# ELOAD.net
KiCad netlist of a schematic drawn in Altium Designer
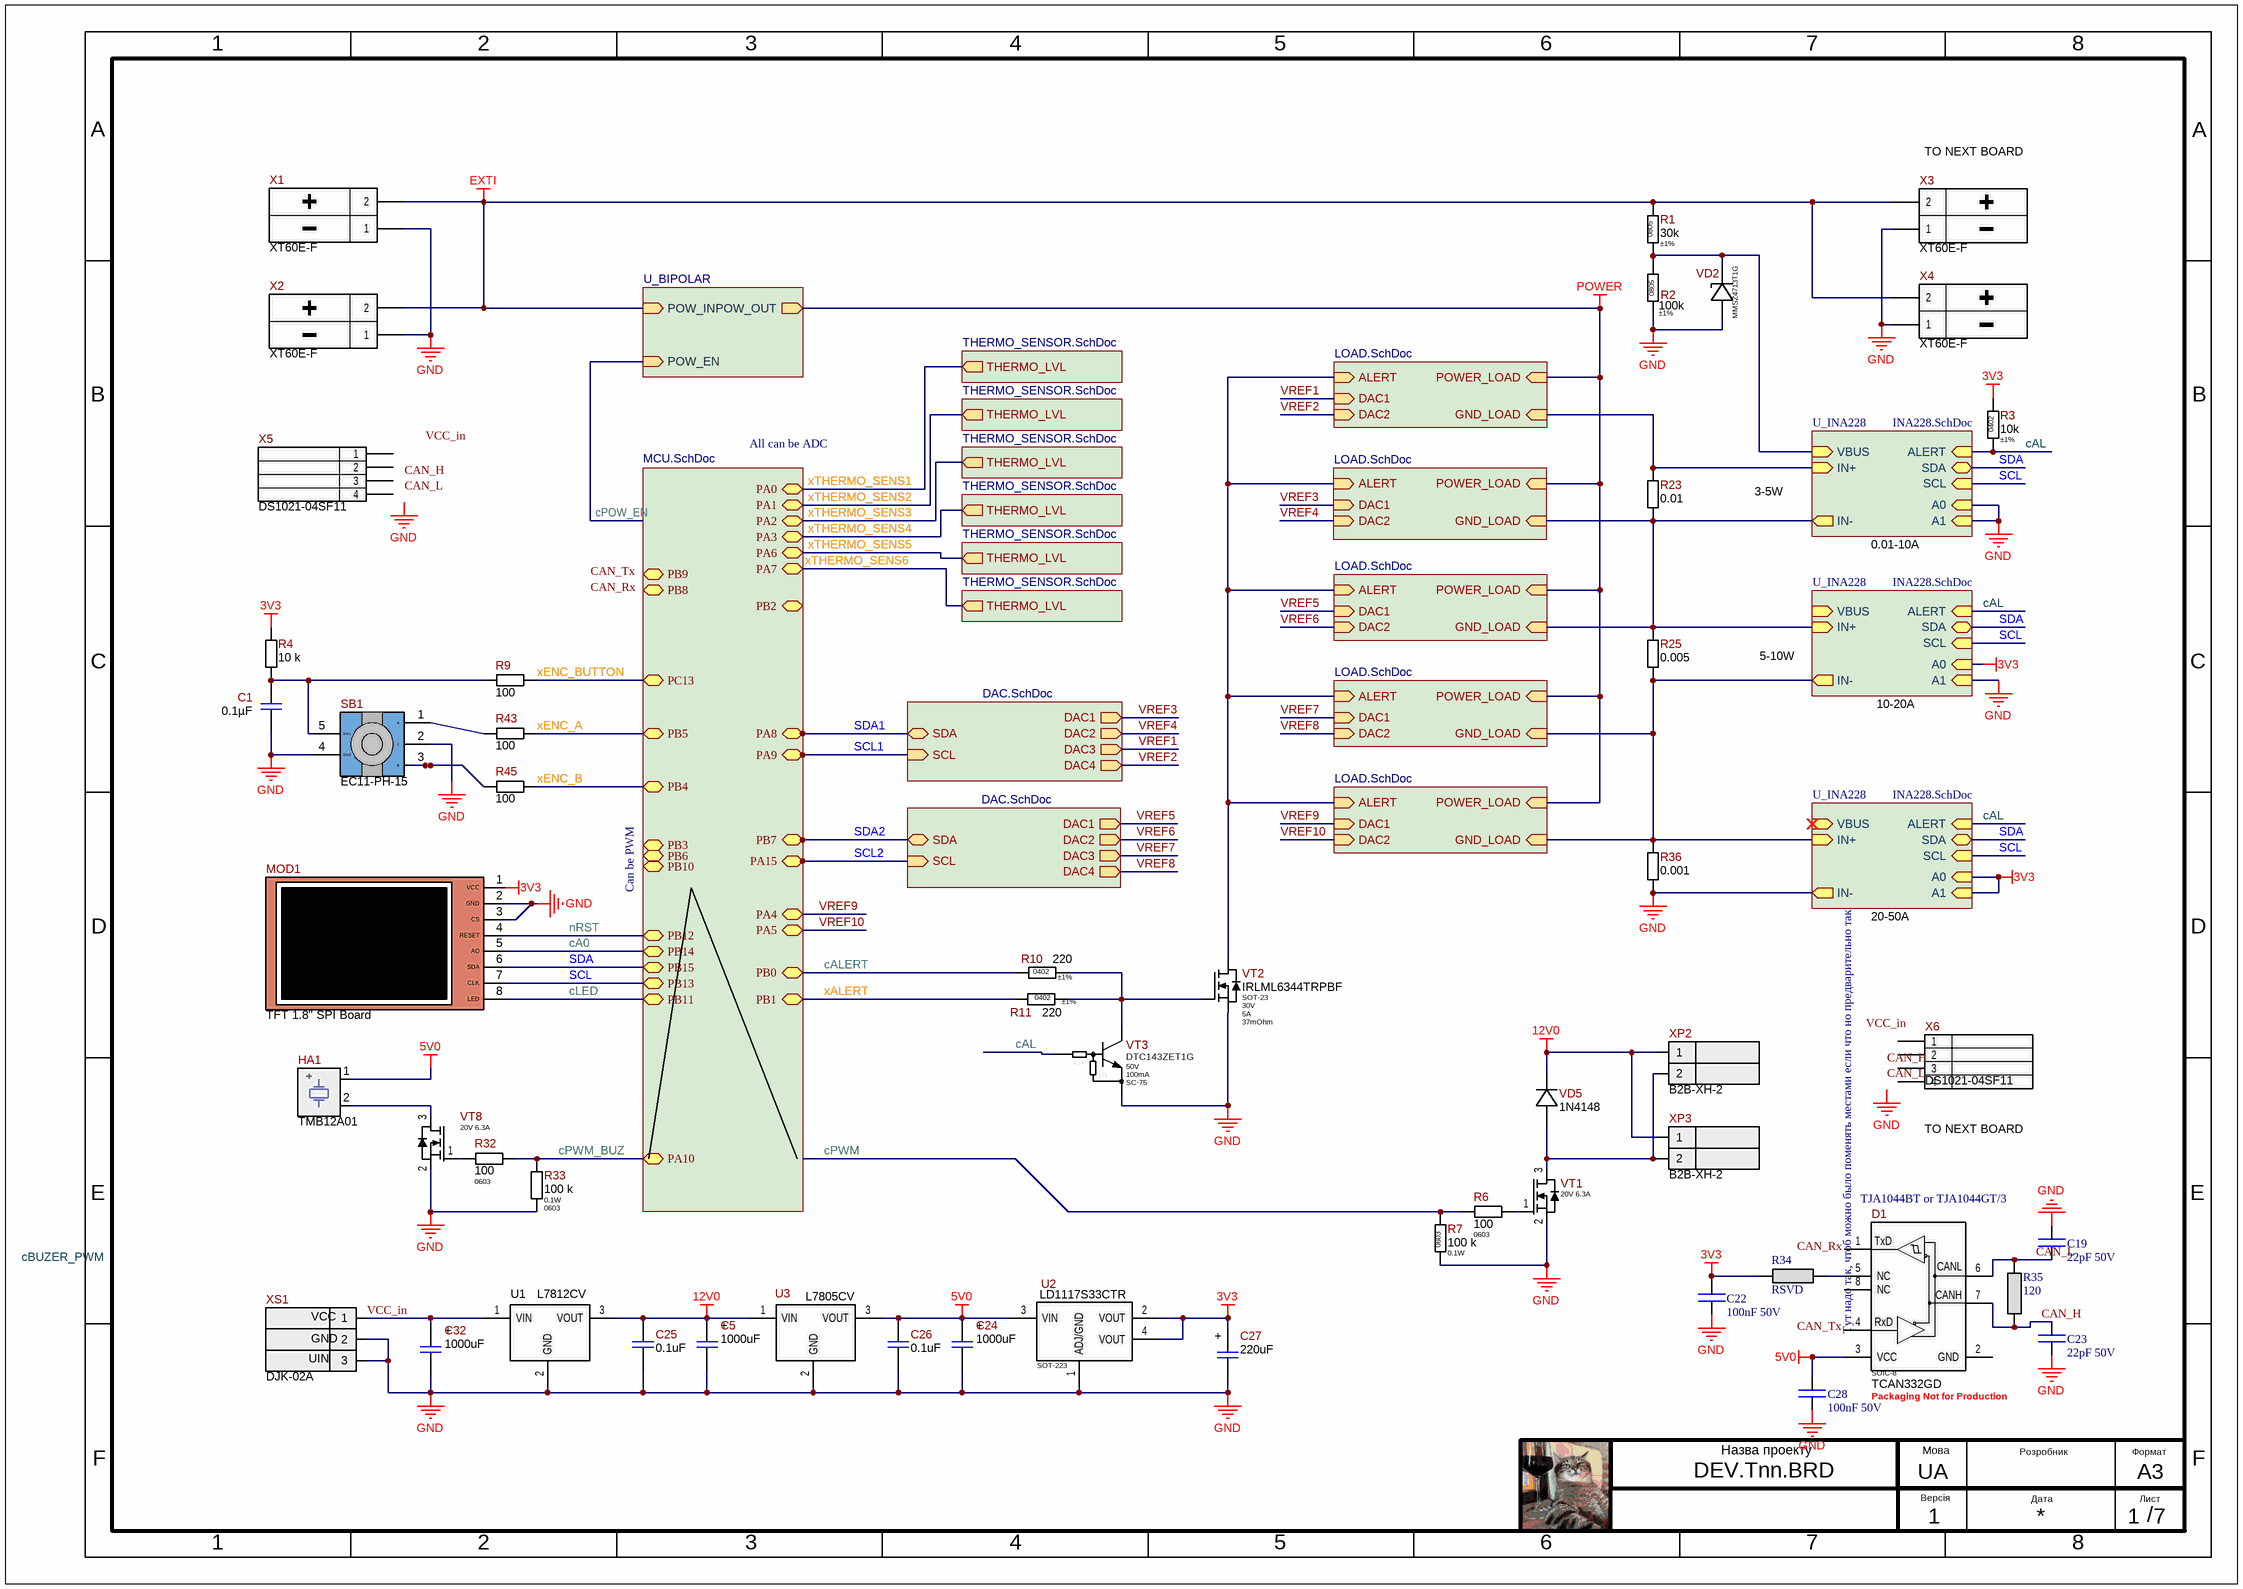
[diagram p0: ELOAD.SchDoc]

(export (version "E")
  (design (tool "Eeschema 10.0.6"))
  (components
    (comp (ref "C1")
      (value "0.1µF")
      (footprint "C0603(1608)")
      (description "CAP CER 0.1UF 50V X7R 0603")
      (fields (field (name "PART NUMBER") "0.1µF  50V C0603") (field (name "TOLERANCE") "±10%"))
      (libsource (lib "Database") (part "Capacitor_Ceramic"))
    )
    (comp (ref "C5")
      (value "1000uF")
      (footprint "CAP 10x16")
      (description "1000uF 20% 16V EHR 10x16mm")
      (fields (field (name "PART NUMBER") "1000uF  16V 10x16(EHR)") (field (name "TOLERANCE") "±20%"))
      (libsource (lib "Database") (part "Capacitor_Electrolytic"))
    )
    (comp (ref "C19")
      (value "22pF 50V")
      (footprint "0805CAP")
      (description "0805 CAP 100nF 50V")
      (libsource (lib "newLib") (part "CAP0805"))
    )
    (comp (ref "C22")
      (value "100nF 50V")
      (footprint "0805CAP")
      (description "0805 CAP 100nF 50V")
      (libsource (lib "newLib") (part "CAP0805"))
    )
    (comp (ref "C23")
      (value "22pF 50V")
      (footprint "0805CAP")
      (description "0805 CAP 100nF 50V")
      (libsource (lib "newLib") (part "CAP0805"))
    )
    (comp (ref "C24")
      (value "1000uF")
      (footprint "CAP 10x16")
      (description "1000uF 20% 16V EHR 10x16mm")
      (fields (field (name "PART NUMBER") "1000uF  16V 10x16(EHR)") (field (name "TOLERANCE") "±20%"))
      (libsource (lib "Database") (part "Capacitor_Electrolytic"))
    )
    (comp (ref "C25")
      (value "0.1uF")
      (footprint "C0603(1608)")
      (description "CAP CER 0.1UF 50V X7R 0603")
      (fields (field (name "PART NUMBER") "0.1uF  50V C0603") (field (name "TOLERANCE") "±10%"))
      (libsource (lib "Database") (part "Capacitor_Ceramic"))
    )
    (comp (ref "C26")
      (value "0.1uF")
      (footprint "C0603(1608)")
      (description "CAP CER 0.1UF 50V X7R 0603")
      (fields (field (name "PART NUMBER") "0.1uF  50V C0603") (field (name "TOLERANCE") "±10%"))
      (libsource (lib "Database") (part "Capacitor_Ceramic"))
    )
    (comp (ref "C27")
      (value "220uF")
      (footprint "CASE_D(7343)")
      (description "CAP TANT 220UF 20% 10V 2917")
      (fields (field (name "PART NUMBER") "220uF  10V CASE-D") (field (name "TOLERANCE") "±20%"))
      (libsource (lib "Database") (part "Capacitor_Electrolytic"))
    )
    (comp (ref "C28")
      (value "100nF 50V")
      (footprint "0805CAP")
      (description "0805 CAP 100nF 50V")
      (libsource (lib "newLib") (part "CAP0805"))
    )
    (comp (ref "C32")
      (value "1000uF")
      (footprint "CAP 10x16")
      (description "1000uF 20% 16V EHR 10x16mm")
      (fields (field (name "PART NUMBER") "1000uF  16V 10x16(EHR)") (field (name "TOLERANCE") "±20%"))
      (libsource (lib "Database") (part "Capacitor_Electrolytic"))
    )
    (comp (ref "D1")
      (value "TCAN332GD")
      (footprint "SOIC-8_W3.9MM")
      (description "3.3V Half Duplex CAN Transceivers with CAN FD, 5 Mbps, SOIC-8")
      (fields
        (field (name "PACKAGE") "SOIC-8")
        (field (name "PART NUMBER") "TCAN332GD")
        (field (name "LIFECYCLE") "Packaging Not for Production")
        (field (name "MANUFACTURER") "Texas Instruments")
      )
      (libsource (lib "AjaxLibrary") (part "TCAN332xx"))
    )
    (comp (ref "HA1")
      (value "TMB12A01")
      (footprint "KPX-1205A")
      (description "AUDIO MAGNETIC 1.2-2.5 V")
      (libsource (lib "Database") (part "BUZ"))
    )
    (comp (ref "MOD1")
      (value "TFT 1.8\" SPI Board")
      (footprint "1.8_TFT_BOARD")
      (description "Display Board TFT 1.8\" SPI Driver ST7735S with SD")
      (libsource (lib "Database") (part "DIS_TFT_1.8"))
    )
    (comp (ref "R1")
      (value "30k")
      (footprint "R_ANY_CHIP_0805_MED")
      (description "30 kOhms ±1%, 1/8W 0805 Thick Film Resistor")
      (fields
        (field (name "TOLERANCE") "±1%")
        (field (name "PACKAGE") "0805")
        (field (name "PART NUMBER") "RC0805FR-0730KL")
        (field (name "MANUFACTURER") "Yageo")
      )
      (libsource (lib "AjaxLibrary") (part "Resistor"))
    )
    (comp (ref "R2")
      (value "100k")
      (footprint "R_ANY_CHIP_0805_MED")
      (description "100 kOhms ±1%, 1/8W 0805 Thick Film Resistor")
      (fields
        (field (name "TOLERANCE") "±1%")
        (field (name "PACKAGE") "0805")
        (field (name "PART NUMBER") "RC0805FR-07100KL")
        (field (name "MANUFACTURER") "Yageo")
      )
      (libsource (lib "AjaxLibrary") (part "Resistor"))
    )
    (comp (ref "R3")
      (value "10k")
      (footprint "R_ANY_CHIP_0402_MED")
      (description "220 Ohms ±1% 1/16W 0402 Thick Film Resistor")
      (fields
        (field (name "TOLERANCE") "±1%")
        (field (name "PACKAGE") "0402")
        (field (name "PART NUMBER") "RC0402FR-07220RL")
        (field (name "MANUFACTURER") "Yageo")
      )
      (libsource (lib "AjaxLibrary") (part "Resistor"))
    )
    (comp (ref "R4")
      (value "10 k")
      (footprint "R0603")
      (description "RES SMD 10 k OHM  ±1% 1/10W 0603")
      (fields (field (name "PART NUMBER") "10 k  R0603"))
      (libsource (lib "Database") (part "R0603"))
    )
    (comp (ref "R6")
      (value "100")
      (footprint "R0603")
      (description "RES SMD 100 OHM  ±1% 1/10W 0603")
      (fields
        (field (name "PACKAGE/CASE") "0603")
        (field (name "PART NUMBER") "100  R0603")
        (field (name "TOLERANCE") "±1%")
      )
      (libsource (lib "Database") (part "R0603"))
    )
    (comp (ref "R7")
      (value "100 k")
      (footprint "R0603")
      (description "RES SMD 100 k OHM  ±1% 1/10W 0603")
      (fields
        (field (name "POWER RATING") "0.1W")
        (field (name "PACKAGE/CASE") "0603")
        (field (name "PART NUMBER") "100 k  R0603")
        (field (name "TOLERANCE") "±1%")
      )
      (libsource (lib "Database") (part "R0603"))
    )
    (comp (ref "R9")
      (value "100")
      (footprint "R0603")
      (description "RES SMD 100 OHM  ±1% 1/10W 0603")
      (fields (field (name "PART NUMBER") "100  R0603") (field (name "TOLERANCE") "±1%"))
      (libsource (lib "Database") (part "R0603"))
    )
    (comp (ref "R10")
      (value "220")
      (footprint "R_ANY_CHIP_0402_MED")
      (description "220 Ohms ±1% 1/16W 0402 Thick Film Resistor")
      (fields
        (field (name "TOLERANCE") "±1%")
        (field (name "PACKAGE") "0402")
        (field (name "PART NUMBER") "RC0402FR-07220RL")
        (field (name "MANUFACTURER") "Yageo")
      )
      (libsource (lib "AjaxLibrary") (part "Resistor"))
    )
    (comp (ref "R11")
      (value "220")
      (footprint "R_ANY_CHIP_0402_MED")
      (description "220 Ohms ±1% 1/16W 0402 Thick Film Resistor")
      (fields
        (field (name "TOLERANCE") "±1%")
        (field (name "PACKAGE") "0402")
        (field (name "PART NUMBER") "RC0402FR-07220RL")
        (field (name "MANUFACTURER") "Yageo")
      )
      (libsource (lib "AjaxLibrary") (part "Resistor"))
    )
    (comp (ref "R23")
      (value "0.01")
      (footprint "SHUNT10")
      (description "SHUNT")
      (fields (field (name "PART NUMBER") "0.001  Resistor") (field (name "TOLERANCE") "±5%"))
      (libsource (lib "Database") (part "RESISTOR"))
    )
    (comp (ref "R25")
      (value "0.005")
      (footprint "SHUNT10")
      (description "SHUNT")
      (fields (field (name "PART NUMBER") "0.001  Resistor") (field (name "TOLERANCE") "±5%"))
      (libsource (lib "Database") (part "RESISTOR"))
    )
    (comp (ref "R32")
      (value "100")
      (footprint "R0603")
      (description "RES SMD 100 OHM  ±1% 1/10W 0603")
      (fields
        (field (name "PACKAGE/CASE") "0603")
        (field (name "PART NUMBER") "100  R0603")
        (field (name "TOLERANCE") "±1%")
      )
      (libsource (lib "Database") (part "R0603"))
    )
    (comp (ref "R33")
      (value "100 k")
      (footprint "R0603")
      (description "RES SMD 100 k OHM  ±1% 1/10W 0603")
      (fields
        (field (name "POWER RATING") "0.1W")
        (field (name "PACKAGE/CASE") "0603")
        (field (name "PART NUMBER") "100 k  R0603")
        (field (name "TOLERANCE") "±1%")
      )
      (libsource (lib "Database") (part "R0603"))
    )
    (comp (ref "R34")
      (value "RSVD")
      (footprint "RES0402")
      (description "0402 RES 10k")
      (libsource (lib "newLib") (part "RES0402"))
    )
    (comp (ref "R35")
      (value "120")
      (footprint "Res0805")
      (description "0805 RES 120")
      (libsource (lib "newLib") (part "RES0805"))
    )
    (comp (ref "R36")
      (value "0.001")
      (footprint "SHUNT10")
      (description "SHUNT")
      (fields (field (name "PART NUMBER") "0.001  Resistor") (field (name "TOLERANCE") "±5%"))
      (libsource (lib "Database") (part "RESISTOR"))
    )
    (comp (ref "R43")
      (value "100")
      (footprint "R0603")
      (description "RES SMD 100 OHM  ±1% 1/10W 0603")
      (fields (field (name "PART NUMBER") "100  R0603") (field (name "TOLERANCE") "±1%"))
      (libsource (lib "Database") (part "R0603"))
    )
    (comp (ref "R45")
      (value "100")
      (footprint "R0603")
      (description "RES SMD 100 OHM  ±1% 1/10W 0603")
      (fields (field (name "PART NUMBER") "100  R0603") (field (name "TOLERANCE") "±1%"))
      (libsource (lib "Database") (part "R0603"))
    )
    (comp (ref "SB1")
      (value "EC11-PH-15")
      (footprint "EC11-PH-15")
      (description "Alps Alpine")
      (libsource (lib "Database") (part "Encoder"))
    )
    (comp (ref "U1")
      (value "L7812CV")
      (footprint "TO220-AB-H")
      (description "IC REG LINEAR 12V 500MA DPAK")
      (fields (field (name "MANUFACTURER") "STMicroelectronics"))
      (libsource (lib "Database") (part "L78"))
    )
    (comp (ref "U2")
      (value "LD1117STR")
      (footprint "SOT223")
      (description "IC REG LINEAR 3.3V 800MA SOT223")
      (fields
        (field (name "MANUFACTURER") "STMicroelectronics")
        (field (name "PACKAGE") "SOT-223")
        (field (name "PART NUMBER") "LD1117S33CTR")
      )
      (libsource (lib "Database") (part "LD1117S"))
    )
    (comp (ref "U3")
      (value "L7805CV")
      (footprint "DPAK")
      (description "IC REG LINEAR 5V 1.5A DPAK")
      (fields (field (name "MANUFACTURER") "STMicroelectronics"))
      (libsource (lib "Database") (part "L78"))
    )
    (comp (ref "VD2")
      (value "MMSZ4713T1G")
      (footprint "SOD-123_MED")
      (description "Zener Diode 30V, 500mW, ±5%, SOD-123")
      (fields
        (field (name "PART NUMBER") "MMSZ4713T1G")
        (field (name "VOLTAGE") "30V")
        (field (name "MANUFACTURER") "Onsemi")
      )
      (libsource (lib "AjaxLibrary") (part "Diode-Zener"))
    )
    (comp (ref "VD5")
      (value "1N4148")
      (footprint "D0805")
      (description "DIODE GEN PURP 75V 250MA SOD323")
      (fields (field (name "MANUFACTURER") "Diodes Incorporated"))
      (libsource (lib "Database") (part "DIODE"))
    )
    (comp (ref "VT1")
      (value "IRLML6244")
      (footprint "SOT-23")
      (description "MOSFET N-CH 20V 6.3A SOT-23")
      (fields (field (name "POWER RATING") "20V 6.3A") (field (name "MANUFACTURER") "InfineonTechnologies"))
      (libsource (lib "Database") (part "N_CHANNEL"))
    )
    (comp (ref "VT2")
      (value "IRLML6344")
      (footprint "SOT-23_MED")
      (description "30V, 5A max N-Channel HEXFET MOSFET, 29mOhm @ Vgs = 4.5V")
      (fields
        (field (name "PART NUMBER") "IRLML6344TRPBF")
        (field (name "PACKAGE") "SOT-23")
        (field (name "MANUFACTURER") "Infineon Technologies")
        (field (name "VDS") "30V")
        (field (name "ID") "5A")
        (field (name "RDS") "37mOhm")
      )
      (libsource (lib "AjaxLibrary") (part "MOSFET-N-Channel"))
    )
    (comp (ref "VT3")
      (value "DTC143ZET1G")
      (footprint "SOT-416")
      (description "50V, 100mA Low Vce(sat) NPN Digital Transistor, Pre-Biased 4.7k/47k (with built-in resistors)")
      (fields
        (field (name "PART NUMBER") "DTC143ZET1G")
        (field (name "VCE") "50V")
        (field (name "IC") "100mA")
        (field (name "PACKAGE") "SC-75")
        (field (name "MANUFACTURER") "Onsemi")
      )
      (libsource (lib "AjaxLibrary") (part "DTC143ZET1G"))
    )
    (comp (ref "VT8")
      (value "IRLML6244")
      (footprint "SOT-23")
      (description "MOSFET N-CH 20V 6.3A SOT-23")
      (fields (field (name "POWER RATING") "20V 6.3A") (field (name "MANUFACTURER") "InfineonTechnologies"))
      (libsource (lib "Database") (part "N_CHANNEL"))
    )
    (comp (ref "X1")
      (value "XT60E-F")
      (footprint "XT60E-F")
      (description "2 Pin DC Power Socket, XT60, Female, Straight, Yellow, 30A, 500V, Gold Flash")
      (fields (field (name "PART NUMBER") "XT60E-F") (field (name "MANUFACTURER") "Amass"))
      (libsource (lib "AjaxLibrary") (part "XT60-Series"))
    )
    (comp (ref "X2")
      (value "XT60E-F")
      (footprint "XT60E-F")
      (description "2 Pin DC Power Socket, XT60, Female, Straight, Yellow, 30A, 500V, Gold Flash")
      (fields (field (name "PART NUMBER") "XT60E-F") (field (name "MANUFACTURER") "Amass"))
      (libsource (lib "AjaxLibrary") (part "XT60-Series"))
    )
    (comp (ref "X3")
      (value "XT60E-F")
      (footprint "XT60E-F")
      (description "2 Pin DC Power Socket, XT60, Female, Straight, Yellow, 30A, 500V, Gold Flash")
      (fields (field (name "PART NUMBER") "XT60E-F") (field (name "MANUFACTURER") "Amass"))
      (libsource (lib "") (part "XT60-Series_1"))
    )
    (comp (ref "X4")
      (value "XT60E-F")
      (footprint "XT60E-F")
      (description "2 Pin DC Power Socket, XT60, Female, Straight, Yellow, 30A, 500V, Gold Flash")
      (fields (field (name "PART NUMBER") "XT60E-F") (field (name "MANUFACTURER") "Amass"))
      (libsource (lib "") (part "XT60-Series_1"))
    )
    (comp (ref "X5")
      (value "PLS-4 (Part of PLS-40)")
      (footprint "DS1021-04S")
      (description "4 Pin 2.54mm Male Header, Vertical, 3mm and 6.1mm, PLS-4")
      (fields (field (name "PART NUMBER") "DS1021-04SF11") (field (name "MANUFACTURER") "Connfly"))
      (libsource (lib "") (part "General-4-Pin_1"))
    )
    (comp (ref "X6")
      (value "PLS-4 (Part of PLS-40)")
      (footprint "DS1021-04S")
      (description "4 Pin 2.54mm Male Header, Vertical, 3mm and 6.1mm, PLS-4")
      (fields (field (name "PART NUMBER") "DS1021-04SF11") (field (name "MANUFACTURER") "Connfly"))
      (libsource (lib "AjaxLibrary") (part "General-4-Pin"))
    )
    (comp (ref "XP2")
      (value "B2B-XH-2")
      (footprint "B2B-XH-2")
      (description "CONN HEADER VERT 2POS 2.5MM")
      (fields (field (name "MANUFACTURER") "JSTSalesAmericaInc."))
      (libsource (lib "Database") (part "CON_2"))
    )
    (comp (ref "XP3")
      (value "B2B-XH-2")
      (footprint "B2B-XH-2")
      (description "CONN HEADER VERT 2POS 2.5MM")
      (fields (field (name "MANUFACTURER") "JSTSalesAmericaInc."))
      (libsource (lib "Database") (part "CON_2"))
    )
    (comp (ref "XS1")
      (value "DJK-02A")
      (footprint "DC-140-003")
      (description "DC POWER JACK CONNECTOR 6.3MM")
      (fields (field (name "MANUFACTURER") "KLS"))
      (libsource (lib "Database") (part "DJK-02A"))
    )
  )
  (nets
    (net (code "1") (name "/ALERT") (class "Default")
      (node (ref "VT2") (pin "3") (pinfunction "D_3") (pintype "passive"))
    )
    (net (code "2") (name "/CAN_H") (class "Default")
      (node (ref "C23") (pin "2") (pinfunction "2_2") (pintype "passive"))
      (node (ref "D1") (pin "7") (pinfunction "CANH_7") (pintype "passive"))
      (node (ref "R35") (pin "1") (pinfunction "1_1") (pintype "passive"))
    )
    (net (code "3") (name "/CAN_L") (class "Default")
      (node (ref "C19") (pin "1") (pinfunction "1_1") (pintype "passive"))
      (node (ref "D1") (pin "6") (pinfunction "CANL_6") (pintype "passive"))
      (node (ref "R35") (pin "2") (pinfunction "2_2") (pintype "passive"))
    )
    (net (code "6") (name "/GND_LOAD") (class "Default")
      (node (ref "R23") (pin "2") (pinfunction "2_2") (pintype "passive"))
    )
    (net (code "7") (name "/IN-") (class "Default")
      (node (ref "R23") (pin "1") (pinfunction "1_1") (pintype "passive"))
      (node (ref "R25") (pin "2") (pinfunction "2_2") (pintype "passive"))
    )
    (net (code "8") (name "/IN-_1") (class "Default")
      (node (ref "R25") (pin "1") (pinfunction "1_1") (pintype "passive"))
      (node (ref "R36") (pin "2") (pinfunction "2_2") (pintype "passive"))
    )
    (net (code "15") (name "/SCL") (class "Default")
      (node (ref "MOD1") (pin "7") (pinfunction "CLK_7") (pintype "passive"))
    )
    (net (code "18") (name "/SDA") (class "Default")
      (node (ref "MOD1") (pin "6") (pinfunction "SDA_6") (pintype "passive"))
    )
    (net (code "22") (name "/VBUS_1") (class "Default")
      (node (ref "R1") (pin "2") (pintype "passive"))
      (node (ref "R2") (pin "1") (pintype "passive"))
      (node (ref "VD2") (pin "CA") (pintype "passive"))
    )
    (net (code "24") (name "/VCC_in") (class "Default")
      (node (ref "C32") (pin "1") (pinfunction "1_1") (pintype "passive"))
      (node (ref "U1") (pin "1") (pinfunction "VIN_1") (pintype "passive"))
      (node (ref "XS1") (pin "1") (pinfunction "1_1") (pintype "passive"))
    )
    (net (code "35") (name "/cA0") (class "Default")
      (node (ref "MOD1") (pin "5") (pinfunction "AO_5") (pintype "passive"))
    )
    (net (code "36") (name "/cAL") (class "Default")
      (node (ref "R3") (pin "2") (pintype "passive"))
      (node (ref "VT3") (pin "1") (pinfunction "B_1") (pintype "passive"))
    )
    (net (code "37") (name "/cALERT") (class "Default") (node (ref "R10") (pin "1") (pintype "passive")))
    (net (code "39") (name "/cLED") (class "Default")
      (node (ref "MOD1") (pin "8") (pinfunction "LED_8") (pintype "passive"))
    )
    (net (code "41") (name "/cPWM") (class "Default")
      (node (ref "R6") (pin "1") (pinfunction "1_1") (pintype "passive"))
      (node (ref "R7") (pin "2") (pinfunction "2_2") (pintype "passive"))
    )
    (net (code "42") (name "/cPWM_BUZ") (class "Default")
      (node (ref "R32") (pin "1") (pinfunction "1_1") (pintype "passive"))
      (node (ref "R33") (pin "2") (pinfunction "2_2") (pintype "passive"))
    )
    (net (code "43") (name "/nRST") (class "Default")
      (node (ref "MOD1") (pin "4") (pinfunction "RESET_4") (pintype "passive"))
    )
    (net (code "44") (name "/xALERT") (class "Default") (node (ref "R11") (pin "1") (pintype "passive")))
    (net (code "45") (name "/xENC_A") (class "Default")
      (node (ref "R43") (pin "2") (pinfunction "2_2") (pintype "passive"))
    )
    (net (code "46") (name "/xENC_B") (class "Default")
      (node (ref "R45") (pin "2") (pinfunction "2_2") (pintype "passive"))
    )
    (net (code "47") (name "/xENC_BUTTON") (class "Default")
      (node (ref "R9") (pin "2") (pinfunction "2_2") (pintype "passive"))
    )
    (net (code "54") (name "3V3") (class "Default")
      (node (ref "C22") (pin "2") (pinfunction "2_2") (pintype "passive"))
      (node (ref "C27") (pin "1") (pinfunction "1_1") (pintype "passive"))
      (node (ref "MOD1") (pin "1") (pinfunction "VCC_1") (pintype "passive"))
      (node (ref "R3") (pin "1") (pintype "passive"))
      (node (ref "R34") (pin "1") (pinfunction "1_1") (pintype "passive"))
      (node (ref "R4") (pin "2") (pinfunction "2_2") (pintype "passive"))
      (node (ref "U2") (pin "2") (pinfunction "VOUT_2") (pintype "passive"))
      (node (ref "U2") (pin "4") (pinfunction "VOUT_4") (pintype "passive"))
    )
    (net (code "55") (name "5V0") (class "Default")
      (node (ref "C24") (pin "1") (pinfunction "1_1") (pintype "passive"))
      (node (ref "C26") (pin "1") (pinfunction "1_1") (pintype "passive"))
      (node (ref "C28") (pin "2") (pinfunction "2_2") (pintype "passive"))
      (node (ref "D1") (pin "3") (pinfunction "VCC_3") (pintype "passive"))
      (node (ref "HA1") (pin "1") (pinfunction "Vcc_1") (pintype "passive"))
      (node (ref "U2") (pin "3") (pinfunction "VIN_3") (pintype "passive"))
      (node (ref "U3") (pin "3") (pinfunction "VOUT_3") (pintype "passive"))
    )
    (net (code "56") (name "12V0") (class "Default")
      (node (ref "C25") (pin "1") (pinfunction "1_1") (pintype "passive"))
      (node (ref "C5") (pin "1") (pinfunction "1_1") (pintype "passive"))
      (node (ref "U1") (pin "3") (pinfunction "VOUT_3") (pintype "passive"))
      (node (ref "U3") (pin "1") (pinfunction "VIN_1") (pintype "passive"))
      (node (ref "VD5") (pin "1") (pinfunction "K_1") (pintype "passive"))
      (node (ref "XP2") (pin "1") (pinfunction "1_1") (pintype "passive"))
      (node (ref "XP3") (pin "1") (pinfunction "1_1") (pintype "passive"))
    )
    (net (code "57") (name "EXTI") (class "Default")
      (node (ref "R1") (pin "1") (pintype "passive"))
      (node (ref "X1") (pin "2") (pinfunction "2_2") (pintype "passive"))
      (node (ref "X2") (pin "2") (pinfunction "2_2") (pintype "passive"))
      (node (ref "X3") (pin "2") (pinfunction "2_2") (pintype "passive"))
      (node (ref "X4") (pin "2") (pinfunction "2_2") (pintype "passive"))
    )
    (net (code "58") (name "GND") (class "Default")
      (node (ref "C1") (pin "2") (pinfunction "2_2") (pintype "passive"))
      (node (ref "C19") (pin "2") (pinfunction "2_2") (pintype "passive"))
      (node (ref "C22") (pin "1") (pinfunction "1_1") (pintype "passive"))
      (node (ref "C23") (pin "1") (pinfunction "1_1") (pintype "passive"))
      (node (ref "C24") (pin "2") (pinfunction "2_2") (pintype "passive"))
      (node (ref "C25") (pin "2") (pinfunction "2_2") (pintype "passive"))
      (node (ref "C26") (pin "2") (pinfunction "2_2") (pintype "passive"))
      (node (ref "C27") (pin "2") (pinfunction "2_2") (pintype "passive"))
      (node (ref "C28") (pin "1") (pinfunction "1_1") (pintype "passive"))
      (node (ref "C32") (pin "2") (pinfunction "2_2") (pintype "passive"))
      (node (ref "C5") (pin "2") (pinfunction "2_2") (pintype "passive"))
      (node (ref "MOD1") (pin "2") (pinfunction "GND_2") (pintype "passive"))
      (node (ref "MOD1") (pin "3") (pinfunction "CS_3") (pintype "passive"))
      (node (ref "R2") (pin "2") (pintype "passive"))
      (node (ref "R33") (pin "1") (pinfunction "1_1") (pintype "passive"))
      (node (ref "R36") (pin "1") (pinfunction "1_1") (pintype "passive"))
      (node (ref "R7") (pin "1") (pinfunction "1_1") (pintype "passive"))
      (node (ref "SB1") (pin "2") (pinfunction "C_2") (pintype "passive"))
      (node (ref "SB1") (pin "4") (pinfunction "SW2_4") (pintype "passive"))
      (node (ref "U1") (pin "2") (pinfunction "GND_2") (pintype "passive"))
      (node (ref "U2") (pin "1") (pinfunction "ADJ/GND_1") (pintype "passive"))
      (node (ref "U3") (pin "2") (pinfunction "GND_2") (pintype "passive"))
      (node (ref "VD2") (pin "AN") (pintype "passive"))
      (node (ref "VT1") (pin "2") (pinfunction "S_2") (pintype "passive"))
      (node (ref "VT2") (pin "2") (pinfunction "S_2") (pintype "passive"))
      (node (ref "VT3") (pin "2") (pinfunction "E_2") (pintype "passive"))
      (node (ref "VT8") (pin "2") (pinfunction "S_2") (pintype "passive"))
      (node (ref "X1") (pin "1") (pinfunction "1_1") (pintype "passive"))
      (node (ref "X2") (pin "1") (pinfunction "1_1") (pintype "passive"))
      (node (ref "X3") (pin "1") (pinfunction "1_1") (pintype "passive"))
      (node (ref "X4") (pin "1") (pinfunction "1_1") (pintype "passive"))
      (node (ref "XS1") (pin "2") (pinfunction "2_2") (pintype "passive"))
      (node (ref "XS1") (pin "3") (pinfunction "3_3") (pintype "passive"))
    )
    (net (code "59") (name "Net-(D1-NC-Pad5)") (class "Default")
      (node (ref "D1") (pin "5") (pinfunction "NC_5") (pintype "passive"))
      (node (ref "R34") (pin "2") (pinfunction "2_2") (pintype "passive"))
    )
    (net (code "60") (name "Net-(HA1-GND)") (class "Default")
      (node (ref "HA1") (pin "2") (pinfunction "GND_2") (pintype "passive"))
      (node (ref "VT8") (pin "3") (pinfunction "D_3") (pintype "passive"))
    )
    (net (code "61") (name "Net-(SB1-A)") (class "Default")
      (node (ref "R43") (pin "1") (pinfunction "1_1") (pintype "passive"))
      (node (ref "SB1") (pin "1") (pinfunction "A_1") (pintype "passive"))
    )
    (net (code "62") (name "Net-(SB1-B)") (class "Default")
      (node (ref "R45") (pin "1") (pinfunction "1_1") (pintype "passive"))
      (node (ref "SB1") (pin "3") (pinfunction "B_3") (pintype "passive"))
    )
    (net (code "63") (name "Net-(SB1-SW1)") (class "Default")
      (node (ref "C1") (pin "1") (pinfunction "1_1") (pintype "passive"))
      (node (ref "R4") (pin "1") (pinfunction "1_1") (pintype "passive"))
      (node (ref "R9") (pin "1") (pinfunction "1_1") (pintype "passive"))
      (node (ref "SB1") (pin "5") (pinfunction "SW1_5") (pintype "passive"))
    )
    (net (code "64") (name "Net-(VD5-A)") (class "Default")
      (node (ref "VD5") (pin "2") (pinfunction "A_2") (pintype "passive"))
      (node (ref "VT1") (pin "3") (pinfunction "D_3") (pintype "passive"))
      (node (ref "XP2") (pin "2") (pinfunction "2_2") (pintype "passive"))
      (node (ref "XP3") (pin "2") (pinfunction "2_2") (pintype "passive"))
    )
    (net (code "65") (name "Net-(VT1-G)") (class "Default")
      (node (ref "R6") (pin "2") (pinfunction "2_2") (pintype "passive"))
      (node (ref "VT1") (pin "1") (pinfunction "G_1") (pintype "passive"))
    )
    (net (code "66") (name "Net-(VT2-G)") (class "Default")
      (node (ref "R10") (pin "2") (pintype "passive"))
      (node (ref "R11") (pin "2") (pintype "passive"))
      (node (ref "VT2") (pin "1") (pinfunction "G_1") (pintype "passive"))
      (node (ref "VT3") (pin "3") (pinfunction "C_3") (pintype "passive"))
    )
    (net (code "67") (name "Net-(VT8-G)") (class "Default")
      (node (ref "R32") (pin "2") (pinfunction "2_2") (pintype "passive"))
      (node (ref "VT8") (pin "1") (pinfunction "G_1") (pintype "passive"))
    )
    (net (code "69") (name "unconnected-(D1-GND-Pad2)") (class "Default")
      (node (ref "D1") (pin "2") (pinfunction "GND_2") (pintype "passive"))
    )
    (net (code "70") (name "unconnected-(D1-NC-Pad8)") (class "Default")
      (node (ref "D1") (pin "8") (pinfunction "NC_8") (pintype "passive"))
    )
    (net (code "71") (name "unconnected-(D1-RxD-Pad4)") (class "Default")
      (node (ref "D1") (pin "4") (pinfunction "RxD_4") (pintype "passive"))
    )
    (net (code "72") (name "unconnected-(D1-TxD-Pad1)") (class "Default")
      (node (ref "D1") (pin "1") (pinfunction "TxD_1") (pintype "passive"))
    )
    (net (code "73") (name "unconnected-(X5-Pad1)") (class "Default")
      (node (ref "X5") (pin "1") (pinfunction "1_1") (pintype "passive"))
    )
    (net (code "74") (name "unconnected-(X5-Pad2)") (class "Default")
      (node (ref "X5") (pin "2") (pinfunction "2_2") (pintype "passive"))
    )
    (net (code "75") (name "unconnected-(X5-Pad3)") (class "Default")
      (node (ref "X5") (pin "3") (pinfunction "3_3") (pintype "passive"))
    )
    (net (code "76") (name "unconnected-(X5-Pad4)") (class "Default")
      (node (ref "X5") (pin "4") (pinfunction "4_4") (pintype "passive"))
    )
    (net (code "77") (name "unconnected-(X6-Pad1)") (class "Default")
      (node (ref "X6") (pin "1") (pinfunction "1_1") (pintype "passive"))
    )
    (net (code "78") (name "unconnected-(X6-Pad2)") (class "Default")
      (node (ref "X6") (pin "2") (pinfunction "2_2") (pintype "passive"))
    )
    (net (code "79") (name "unconnected-(X6-Pad3)") (class "Default")
      (node (ref "X6") (pin "3") (pinfunction "3_3") (pintype "passive"))
    )
    (net (code "80") (name "unconnected-(X6-Pad4)") (class "Default")
      (node (ref "X6") (pin "4") (pinfunction "4_4") (pintype "passive"))
    )
  )
)
